# PALFromPerl.net
KiCad netlist of a schematic drawn in EAGLE
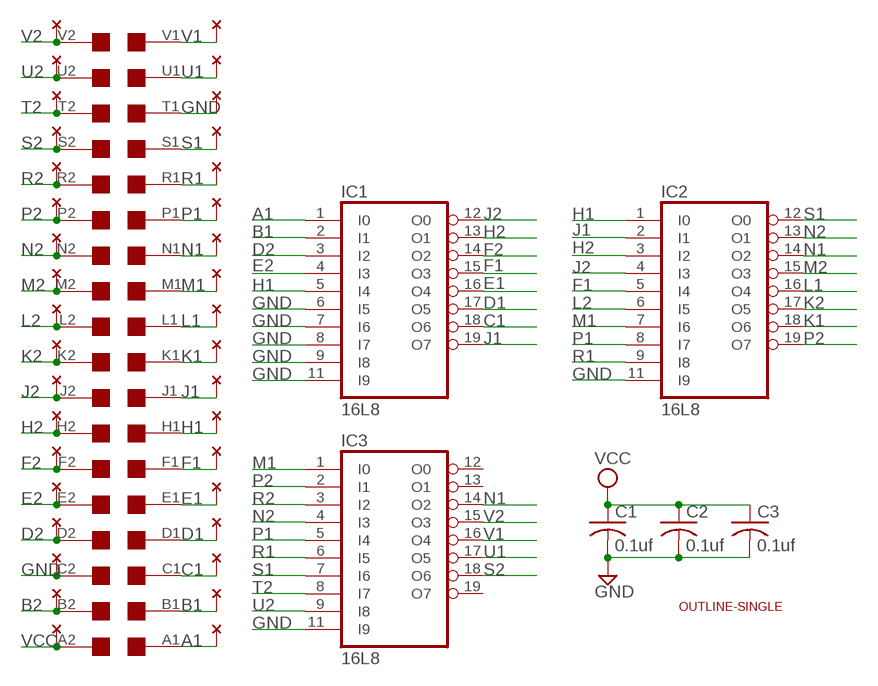
[diagram p0: schematic, sheet 1]

(export (version "E")
  (design (tool "Eeschema 10.0.6"))
  (components
    (comp (ref "C1")
      (value "0.1uf")
      (footprint "eagle-import:C050-025X075")
      (libsource (lib "eagle-import") (part "C-US050-025X075"))
    )
    (comp (ref "C2")
      (value "0.1uf")
      (footprint "eagle-import:C050-025X075")
      (libsource (lib "eagle-import") (part "C-US050-025X075"))
    )
    (comp (ref "C3")
      (value "0.1uf")
      (footprint "eagle-import:C050-025X075")
      (libsource (lib "eagle-import") (part "C-US050-025X075"))
    )
    (comp (ref "IC1")
      (value "16L8")
      (footprint "eagle-import:DIL20")
      (fields (field (name "MF") "TEXAS INSTRUMENTS") (field (name "MPN") "TIBPAL16L8-7CN"))
      (libsource (lib "eagle-import") (part "16L8"))
    )
    (comp (ref "IC2")
      (value "16L8")
      (footprint "eagle-import:DIL20")
      (fields (field (name "MF") "TEXAS INSTRUMENTS") (field (name "MPN") "TIBPAL16L8-7CN"))
      (libsource (lib "eagle-import") (part "16L8"))
    )
    (comp (ref "IC3")
      (value "16L8")
      (footprint "eagle-import:DIL20")
      (fields (field (name "MF") "TEXAS INSTRUMENTS") (field (name "MPN") "TIBPAL16L8-7CN"))
      (libsource (lib "eagle-import") (part "16L8"))
    )
    (comp (ref "U$1")
      (value "EDGE-2CONNECTOR")
      (footprint "eagle-import:EDGE-CON2")
      (libsource (lib "eagle-import") (part "EDGE-2CONNECTOR"))
    )
    (comp (ref "U$2")
      (value "OUTLINE-SINGLE")
      (footprint "eagle-import:SINGLE")
      (libsource (lib "eagle-import") (part "OUTLINE-SINGLE"))
    )
    (comp (ref "U$4")
      (value "THRU-HOLE2A")
      (footprint "eagle-import:THRU-HOLEA")
      (libsource (lib "eagle-import") (part "THRU-HOLE2A"))
    )
  )
  (nets
    (net (code "1") (name "/A1") (class "Default")
      (node (ref "IC1") (pin "1") (pinfunction "I0_1") (pintype "input"))
      (node (ref "U$1") (pin "A1") (pinfunction "1_A1") (pintype "bidirectional"))
      (node (ref "U$4") (pin "A1") (pinfunction "P$1_A1") (pintype "passive"))
    )
    (net (code "2") (name "/B1") (class "Default")
      (node (ref "IC1") (pin "2") (pinfunction "I1_2") (pintype "input"))
      (node (ref "U$1") (pin "B1") (pinfunction "1_B1") (pintype "bidirectional"))
      (node (ref "U$4") (pin "B1") (pinfunction "P$1_B1") (pintype "passive"))
    )
    (net (code "3") (name "/B2") (class "Default")
      (node (ref "U$1") (pin "B2") (pinfunction "1_B2") (pintype "bidirectional"))
      (node (ref "U$4") (pin "B2") (pinfunction "P$1_B2") (pintype "passive"))
    )
    (net (code "4") (name "/C1") (class "Default")
      (node (ref "IC1") (pin "18") (pinfunction "O6_18") (pintype "bidirectional"))
      (node (ref "U$1") (pin "C1") (pinfunction "1_C1") (pintype "bidirectional"))
      (node (ref "U$4") (pin "C1") (pinfunction "P$1_C1") (pintype "passive"))
    )
    (net (code "5") (name "/D1") (class "Default")
      (node (ref "IC1") (pin "17") (pinfunction "O5_17") (pintype "bidirectional"))
      (node (ref "U$1") (pin "D1") (pinfunction "1_D1") (pintype "bidirectional"))
      (node (ref "U$4") (pin "D1") (pinfunction "P$1_D1") (pintype "passive"))
    )
    (net (code "6") (name "/D2") (class "Default")
      (node (ref "IC1") (pin "3") (pinfunction "I2_3") (pintype "input"))
      (node (ref "U$1") (pin "D2") (pinfunction "1_D2") (pintype "bidirectional"))
      (node (ref "U$4") (pin "D2") (pinfunction "P$1_D2") (pintype "passive"))
    )
    (net (code "7") (name "/E1") (class "Default")
      (node (ref "IC1") (pin "16") (pinfunction "O4_16") (pintype "bidirectional"))
      (node (ref "U$1") (pin "E1") (pinfunction "1_E1") (pintype "bidirectional"))
      (node (ref "U$4") (pin "E1") (pinfunction "P$1_E1") (pintype "passive"))
    )
    (net (code "8") (name "/E2") (class "Default")
      (node (ref "IC1") (pin "4") (pinfunction "I3_4") (pintype "input"))
      (node (ref "U$1") (pin "E2") (pinfunction "1_E2") (pintype "bidirectional"))
      (node (ref "U$4") (pin "E2") (pinfunction "P$1_E2") (pintype "passive"))
    )
    (net (code "9") (name "/F1") (class "Default")
      (node (ref "IC1") (pin "15") (pinfunction "O3_15") (pintype "bidirectional"))
      (node (ref "IC2") (pin "5") (pinfunction "I4_5") (pintype "input"))
      (node (ref "U$1") (pin "F1") (pinfunction "1_F1") (pintype "bidirectional"))
      (node (ref "U$4") (pin "F1") (pinfunction "P$1_F1") (pintype "passive"))
    )
    (net (code "10") (name "/F2") (class "Default")
      (node (ref "IC1") (pin "14") (pinfunction "O2_14") (pintype "bidirectional"))
      (node (ref "U$1") (pin "F2") (pinfunction "1_F2") (pintype "bidirectional"))
      (node (ref "U$4") (pin "F2") (pinfunction "P$1_F2") (pintype "passive"))
    )
    (net (code "11") (name "/H1") (class "Default")
      (node (ref "IC1") (pin "5") (pinfunction "I4_5") (pintype "input"))
      (node (ref "IC2") (pin "1") (pinfunction "I0_1") (pintype "input"))
      (node (ref "U$1") (pin "H1") (pinfunction "1_H1") (pintype "bidirectional"))
      (node (ref "U$4") (pin "H1") (pinfunction "P$1_H1") (pintype "passive"))
    )
    (net (code "12") (name "/H2") (class "Default")
      (node (ref "IC1") (pin "13") (pinfunction "O1_13") (pintype "bidirectional"))
      (node (ref "IC2") (pin "3") (pinfunction "I2_3") (pintype "input"))
      (node (ref "U$1") (pin "H2") (pinfunction "1_H2") (pintype "bidirectional"))
      (node (ref "U$4") (pin "H2") (pinfunction "P$1_H2") (pintype "passive"))
    )
    (net (code "13") (name "/J1") (class "Default")
      (node (ref "IC1") (pin "19") (pinfunction "O7_19") (pintype "output"))
      (node (ref "IC2") (pin "2") (pinfunction "I1_2") (pintype "input"))
      (node (ref "U$1") (pin "J1") (pinfunction "1_J1") (pintype "bidirectional"))
      (node (ref "U$4") (pin "J1") (pinfunction "P$1_J1") (pintype "passive"))
    )
    (net (code "14") (name "/J2") (class "Default")
      (node (ref "IC1") (pin "12") (pinfunction "O0_12") (pintype "output"))
      (node (ref "IC2") (pin "4") (pinfunction "I3_4") (pintype "input"))
      (node (ref "U$1") (pin "J2") (pinfunction "1_J2") (pintype "bidirectional"))
      (node (ref "U$4") (pin "J2") (pinfunction "P$1_J2") (pintype "passive"))
    )
    (net (code "15") (name "/K1") (class "Default")
      (node (ref "IC2") (pin "18") (pinfunction "O6_18") (pintype "bidirectional"))
      (node (ref "U$1") (pin "K1") (pinfunction "1_K1") (pintype "bidirectional"))
      (node (ref "U$4") (pin "K1") (pinfunction "P$1_K1") (pintype "passive"))
    )
    (net (code "16") (name "/K2") (class "Default")
      (node (ref "IC2") (pin "17") (pinfunction "O5_17") (pintype "bidirectional"))
      (node (ref "U$1") (pin "K2") (pinfunction "1_K2") (pintype "bidirectional"))
      (node (ref "U$4") (pin "K2") (pinfunction "P$1_K2") (pintype "passive"))
    )
    (net (code "17") (name "/L1") (class "Default")
      (node (ref "IC2") (pin "16") (pinfunction "O4_16") (pintype "bidirectional"))
      (node (ref "U$1") (pin "L1") (pinfunction "1_L1") (pintype "bidirectional"))
      (node (ref "U$4") (pin "L1") (pinfunction "P$1_L1") (pintype "passive"))
    )
    (net (code "18") (name "/L2") (class "Default")
      (node (ref "IC2") (pin "6") (pinfunction "I5_6") (pintype "input"))
      (node (ref "U$1") (pin "L2") (pinfunction "1_L2") (pintype "bidirectional"))
      (node (ref "U$4") (pin "L2") (pinfunction "P$1_L2") (pintype "passive"))
    )
    (net (code "19") (name "/M1") (class "Default")
      (node (ref "IC2") (pin "7") (pinfunction "I6_7") (pintype "input"))
      (node (ref "IC3") (pin "1") (pinfunction "I0_1") (pintype "input"))
      (node (ref "U$1") (pin "M1") (pinfunction "1_M1") (pintype "bidirectional"))
      (node (ref "U$4") (pin "M1") (pinfunction "P$1_M1") (pintype "passive"))
    )
    (net (code "20") (name "/M2") (class "Default")
      (node (ref "IC2") (pin "15") (pinfunction "O3_15") (pintype "bidirectional"))
      (node (ref "U$1") (pin "M2") (pinfunction "1_M2") (pintype "bidirectional"))
      (node (ref "U$4") (pin "M2") (pinfunction "P$1_M2") (pintype "passive"))
    )
    (net (code "21") (name "/N1") (class "Default")
      (node (ref "IC2") (pin "14") (pinfunction "O2_14") (pintype "bidirectional"))
      (node (ref "IC3") (pin "14") (pinfunction "O2_14") (pintype "bidirectional"))
      (node (ref "U$1") (pin "N1") (pinfunction "1_N1") (pintype "bidirectional"))
      (node (ref "U$4") (pin "N1") (pinfunction "P$1_N1") (pintype "passive"))
    )
    (net (code "22") (name "/N2") (class "Default")
      (node (ref "IC2") (pin "13") (pinfunction "O1_13") (pintype "bidirectional"))
      (node (ref "IC3") (pin "4") (pinfunction "I3_4") (pintype "input"))
      (node (ref "U$1") (pin "N2") (pinfunction "1_N2") (pintype "bidirectional"))
      (node (ref "U$4") (pin "N2") (pinfunction "P$1_N2") (pintype "passive"))
    )
    (net (code "23") (name "/P1") (class "Default")
      (node (ref "IC2") (pin "8") (pinfunction "I7_8") (pintype "input"))
      (node (ref "IC3") (pin "5") (pinfunction "I4_5") (pintype "input"))
      (node (ref "U$1") (pin "P1") (pinfunction "1_P1") (pintype "bidirectional"))
      (node (ref "U$4") (pin "P1") (pinfunction "P$1_P1") (pintype "passive"))
    )
    (net (code "24") (name "/P2") (class "Default")
      (node (ref "IC2") (pin "19") (pinfunction "O7_19") (pintype "output"))
      (node (ref "IC3") (pin "2") (pinfunction "I1_2") (pintype "input"))
      (node (ref "U$1") (pin "P2") (pinfunction "1_P2") (pintype "bidirectional"))
      (node (ref "U$4") (pin "P2") (pinfunction "P$1_P2") (pintype "passive"))
    )
    (net (code "25") (name "/R1") (class "Default")
      (node (ref "IC2") (pin "9") (pinfunction "I8_9") (pintype "input"))
      (node (ref "IC3") (pin "6") (pinfunction "I5_6") (pintype "input"))
      (node (ref "U$1") (pin "R1") (pinfunction "1_R1") (pintype "bidirectional"))
      (node (ref "U$4") (pin "R1") (pinfunction "P$1_R1") (pintype "passive"))
    )
    (net (code "26") (name "/R2") (class "Default")
      (node (ref "IC3") (pin "3") (pinfunction "I2_3") (pintype "input"))
      (node (ref "U$1") (pin "R2") (pinfunction "1_R2") (pintype "bidirectional"))
      (node (ref "U$4") (pin "R2") (pinfunction "P$1_R2") (pintype "passive"))
    )
    (net (code "27") (name "/S1") (class "Default")
      (node (ref "IC2") (pin "12") (pinfunction "O0_12") (pintype "output"))
      (node (ref "IC3") (pin "7") (pinfunction "I6_7") (pintype "input"))
      (node (ref "U$1") (pin "S1") (pinfunction "1_S1") (pintype "bidirectional"))
      (node (ref "U$4") (pin "S1") (pinfunction "P$1_S1") (pintype "passive"))
    )
    (net (code "28") (name "/S2") (class "Default")
      (node (ref "IC3") (pin "18") (pinfunction "O6_18") (pintype "bidirectional"))
      (node (ref "U$1") (pin "S2") (pinfunction "1_S2") (pintype "bidirectional"))
      (node (ref "U$4") (pin "S2") (pinfunction "P$1_S2") (pintype "passive"))
    )
    (net (code "29") (name "/T2") (class "Default")
      (node (ref "IC3") (pin "8") (pinfunction "I7_8") (pintype "input"))
      (node (ref "U$1") (pin "T2") (pinfunction "1_T2") (pintype "bidirectional"))
      (node (ref "U$4") (pin "T2") (pinfunction "P$1_T2") (pintype "passive"))
    )
    (net (code "30") (name "/U1") (class "Default")
      (node (ref "IC3") (pin "17") (pinfunction "O5_17") (pintype "bidirectional"))
      (node (ref "U$1") (pin "U1") (pinfunction "1_U1") (pintype "bidirectional"))
      (node (ref "U$4") (pin "U1") (pinfunction "P$1_U1") (pintype "passive"))
    )
    (net (code "31") (name "/U2") (class "Default")
      (node (ref "IC3") (pin "9") (pinfunction "I8_9") (pintype "input"))
      (node (ref "U$1") (pin "U2") (pinfunction "1_U2") (pintype "bidirectional"))
      (node (ref "U$4") (pin "U2") (pinfunction "P$1_U2") (pintype "passive"))
    )
    (net (code "32") (name "/V1") (class "Default")
      (node (ref "IC3") (pin "16") (pinfunction "O4_16") (pintype "bidirectional"))
      (node (ref "U$1") (pin "V1") (pinfunction "1_V1") (pintype "bidirectional"))
      (node (ref "U$4") (pin "V1") (pinfunction "P$1_V1") (pintype "passive"))
    )
    (net (code "33") (name "/V2") (class "Default")
      (node (ref "IC3") (pin "15") (pinfunction "O3_15") (pintype "bidirectional"))
      (node (ref "U$1") (pin "V2") (pinfunction "1_V2") (pintype "bidirectional"))
      (node (ref "U$4") (pin "V2") (pinfunction "P$1_V2") (pintype "passive"))
    )
    (net (code "34") (name "GND") (class "Default")
      (node (ref "C1") (pin "2") (pinfunction "2_2") (pintype "passive"))
      (node (ref "C2") (pin "2") (pinfunction "2_2") (pintype "passive"))
      (node (ref "C3") (pin "2") (pinfunction "2_2") (pintype "passive"))
      (node (ref "IC1") (pin "11") (pinfunction "I9_11") (pintype "input"))
      (node (ref "IC1") (pin "6") (pinfunction "I5_6") (pintype "input"))
      (node (ref "IC1") (pin "7") (pinfunction "I6_7") (pintype "input"))
      (node (ref "IC1") (pin "8") (pinfunction "I7_8") (pintype "input"))
      (node (ref "IC1") (pin "9") (pinfunction "I8_9") (pintype "input"))
      (node (ref "IC2") (pin "11") (pinfunction "I9_11") (pintype "input"))
      (node (ref "IC3") (pin "11") (pinfunction "I9_11") (pintype "input"))
      (node (ref "U$1") (pin "C2") (pinfunction "1_C2") (pintype "bidirectional"))
      (node (ref "U$1") (pin "T1") (pinfunction "1_T1") (pintype "bidirectional"))
      (node (ref "U$4") (pin "C2") (pinfunction "P$1_C2") (pintype "passive"))
      (node (ref "U$4") (pin "T1") (pinfunction "P$1_T1") (pintype "passive"))
    )
    (net (code "35") (name "VCC") (class "Default")
      (node (ref "C1") (pin "1") (pinfunction "1_1") (pintype "passive"))
      (node (ref "C2") (pin "1") (pinfunction "1_1") (pintype "passive"))
      (node (ref "C3") (pin "1") (pinfunction "1_1") (pintype "passive"))
      (node (ref "U$1") (pin "A2") (pinfunction "1_A2") (pintype "bidirectional"))
      (node (ref "U$4") (pin "A2") (pinfunction "P$1_A2") (pintype "passive"))
    )
    (net (code "36") (name "unconnected-(IC3A-O0-Pad12)") (class "Default")
      (node (ref "IC3") (pin "12") (pinfunction "O0_12") (pintype "output"))
    )
    (net (code "37") (name "unconnected-(IC3A-O1-Pad13)") (class "Default")
      (node (ref "IC3") (pin "13") (pinfunction "O1_13") (pintype "bidirectional"))
    )
    (net (code "38") (name "unconnected-(IC3A-O7-Pad19)") (class "Default")
      (node (ref "IC3") (pin "19") (pinfunction "O7_19") (pintype "output"))
    )
  )
)
